# Not_Used.net
KiCad netlist of a schematic drawn in Altium Designer
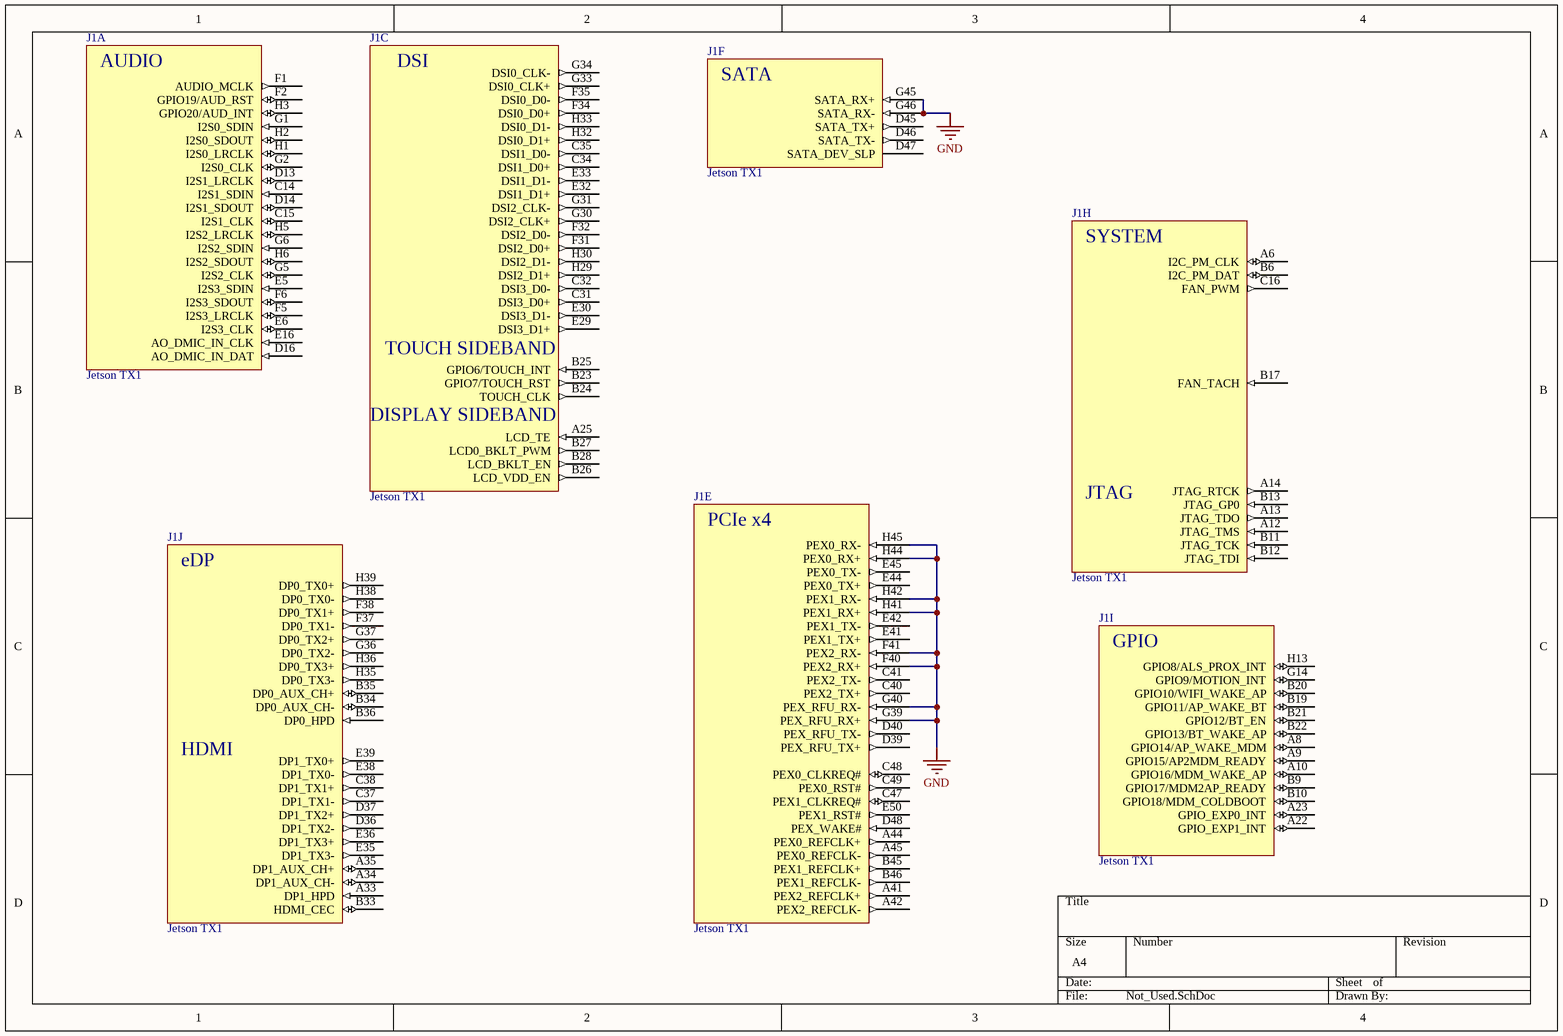
[diagram p0: Not_Used.SchDoc]

(export (version "E")
  (design (tool "Eeschema 10.0.6"))
  (components
    (comp (ref "J1")
      (value "Jetson TX1")
      (footprint "Nvidia Jetson TX1")
      (description "Nvidia computing module")
      (libsource (lib "Modules") (part "NVIDIA_Jetson_TX1"))
    )
  )
  (nets
    (net (code "1") (name "GND") (class "Default")
      (node (ref "J1") (pin "F40") (pinfunction "PEX2_RX+_F40") (pintype "input"))
      (node (ref "J1") (pin "F41") (pinfunction "PEX2_RX-_F41") (pintype "input"))
      (node (ref "J1") (pin "G39") (pinfunction "PEX_RFU_RX+_G39") (pintype "input"))
      (node (ref "J1") (pin "G40") (pinfunction "PEX_RFU_RX-_G40") (pintype "input"))
      (node (ref "J1") (pin "G45") (pinfunction "SATA_RX+_G45") (pintype "input"))
      (node (ref "J1") (pin "G46") (pinfunction "SATA_RX-_G46") (pintype "input"))
      (node (ref "J1") (pin "H41") (pinfunction "PEX1_RX+_H41") (pintype "input"))
      (node (ref "J1") (pin "H42") (pinfunction "PEX1_RX-_H42") (pintype "input"))
      (node (ref "J1") (pin "H44") (pinfunction "PEX0_RX+_H44") (pintype "input"))
      (node (ref "J1") (pin "H45") (pinfunction "PEX0_RX-_H45") (pintype "input"))
    )
    (net (code "2") (name "unconnected-(J1A-AO_DMIC_IN_CLK-PadE16)") (class "Default")
      (node (ref "J1") (pin "E16") (pinfunction "AO_DMIC_IN_CLK_E16") (pintype "input"))
    )
    (net (code "3") (name "unconnected-(J1A-AO_DMIC_IN_DAT-PadD16)") (class "Default")
      (node (ref "J1") (pin "D16") (pinfunction "AO_DMIC_IN_DAT_D16") (pintype "input"))
    )
    (net (code "4") (name "unconnected-(J1A-AUDIO_MCLK-PadF1)") (class "Default")
      (node (ref "J1") (pin "F1") (pinfunction "AUDIO_MCLK_F1") (pintype "output"))
    )
    (net (code "5") (name "unconnected-(J1A-GPIO19{slash}AUD_RST-PadF2)") (class "Default")
      (node (ref "J1") (pin "F2") (pinfunction "GPIO19/AUD_RST_F2") (pintype "bidirectional"))
    )
    (net (code "6") (name "unconnected-(J1A-GPIO20{slash}AUD_INT-PadH3)") (class "Default")
      (node (ref "J1") (pin "H3") (pinfunction "GPIO20/AUD_INT_H3") (pintype "bidirectional"))
    )
    (net (code "7") (name "unconnected-(J1A-I2S0_CLK-PadG2)") (class "Default")
      (node (ref "J1") (pin "G2") (pinfunction "I2S0_CLK_G2") (pintype "bidirectional"))
    )
    (net (code "8") (name "unconnected-(J1A-I2S0_LRCLK-PadH1)") (class "Default")
      (node (ref "J1") (pin "H1") (pinfunction "I2S0_LRCLK_H1") (pintype "bidirectional"))
    )
    (net (code "9") (name "unconnected-(J1A-I2S0_SDIN-PadG1)") (class "Default")
      (node (ref "J1") (pin "G1") (pinfunction "I2S0_SDIN_G1") (pintype "input"))
    )
    (net (code "10") (name "unconnected-(J1A-I2S0_SDOUT-PadH2)") (class "Default")
      (node (ref "J1") (pin "H2") (pinfunction "I2S0_SDOUT_H2") (pintype "bidirectional"))
    )
    (net (code "11") (name "unconnected-(J1A-I2S1_CLK-PadC15)") (class "Default")
      (node (ref "J1") (pin "C15") (pinfunction "I2S1_CLK_C15") (pintype "bidirectional"))
    )
    (net (code "12") (name "unconnected-(J1A-I2S1_LRCLK-PadD13)") (class "Default")
      (node (ref "J1") (pin "D13") (pinfunction "I2S1_LRCLK_D13") (pintype "bidirectional"))
    )
    (net (code "13") (name "unconnected-(J1A-I2S1_SDIN-PadC14)") (class "Default")
      (node (ref "J1") (pin "C14") (pinfunction "I2S1_SDIN_C14") (pintype "input"))
    )
    (net (code "14") (name "unconnected-(J1A-I2S1_SDOUT-PadD14)") (class "Default")
      (node (ref "J1") (pin "D14") (pinfunction "I2S1_SDOUT_D14") (pintype "bidirectional"))
    )
    (net (code "15") (name "unconnected-(J1A-I2S2_CLK-PadG5)") (class "Default")
      (node (ref "J1") (pin "G5") (pinfunction "I2S2_CLK_G5") (pintype "bidirectional"))
    )
    (net (code "16") (name "unconnected-(J1A-I2S2_LRCLK-PadH5)") (class "Default")
      (node (ref "J1") (pin "H5") (pinfunction "I2S2_LRCLK_H5") (pintype "bidirectional"))
    )
    (net (code "17") (name "unconnected-(J1A-I2S2_SDIN-PadG6)") (class "Default")
      (node (ref "J1") (pin "G6") (pinfunction "I2S2_SDIN_G6") (pintype "input"))
    )
    (net (code "18") (name "unconnected-(J1A-I2S2_SDOUT-PadH6)") (class "Default")
      (node (ref "J1") (pin "H6") (pinfunction "I2S2_SDOUT_H6") (pintype "bidirectional"))
    )
    (net (code "19") (name "unconnected-(J1A-I2S3_CLK-PadE6)") (class "Default")
      (node (ref "J1") (pin "E6") (pinfunction "I2S3_CLK_E6") (pintype "bidirectional"))
    )
    (net (code "20") (name "unconnected-(J1A-I2S3_LRCLK-PadF5)") (class "Default")
      (node (ref "J1") (pin "F5") (pinfunction "I2S3_LRCLK_F5") (pintype "bidirectional"))
    )
    (net (code "21") (name "unconnected-(J1A-I2S3_SDIN-PadE5)") (class "Default")
      (node (ref "J1") (pin "E5") (pinfunction "I2S3_SDIN_E5") (pintype "input"))
    )
    (net (code "22") (name "unconnected-(J1A-I2S3_SDOUT-PadF6)") (class "Default")
      (node (ref "J1") (pin "F6") (pinfunction "I2S3_SDOUT_F6") (pintype "bidirectional"))
    )
    (net (code "23") (name "unconnected-(J1C-DSI0_CLK+-PadG33)") (class "Default")
      (node (ref "J1") (pin "G33") (pinfunction "DSI0_CLK+_G33") (pintype "output"))
    )
    (net (code "24") (name "unconnected-(J1C-DSI0_CLK--PadG34)") (class "Default")
      (node (ref "J1") (pin "G34") (pinfunction "DSI0_CLK-_G34") (pintype "output"))
    )
    (net (code "25") (name "unconnected-(J1C-DSI0_D0+-PadF34)") (class "Default")
      (node (ref "J1") (pin "F34") (pinfunction "DSI0_D0+_F34") (pintype "output"))
    )
    (net (code "26") (name "unconnected-(J1C-DSI0_D0--PadF35)") (class "Default")
      (node (ref "J1") (pin "F35") (pinfunction "DSI0_D0-_F35") (pintype "output"))
    )
    (net (code "27") (name "unconnected-(J1C-DSI0_D1+-PadH32)") (class "Default")
      (node (ref "J1") (pin "H32") (pinfunction "DSI0_D1+_H32") (pintype "output"))
    )
    (net (code "28") (name "unconnected-(J1C-DSI0_D1--PadH33)") (class "Default")
      (node (ref "J1") (pin "H33") (pinfunction "DSI0_D1-_H33") (pintype "output"))
    )
    (net (code "29") (name "unconnected-(J1C-DSI1_D0+-PadC34)") (class "Default")
      (node (ref "J1") (pin "C34") (pinfunction "DSI1_D0+_C34") (pintype "output"))
    )
    (net (code "30") (name "unconnected-(J1C-DSI1_D0--PadC35)") (class "Default")
      (node (ref "J1") (pin "C35") (pinfunction "DSI1_D0-_C35") (pintype "output"))
    )
    (net (code "31") (name "unconnected-(J1C-DSI1_D1+-PadE32)") (class "Default")
      (node (ref "J1") (pin "E32") (pinfunction "DSI1_D1+_E32") (pintype "output"))
    )
    (net (code "32") (name "unconnected-(J1C-DSI1_D1--PadE33)") (class "Default")
      (node (ref "J1") (pin "E33") (pinfunction "DSI1_D1-_E33") (pintype "output"))
    )
    (net (code "33") (name "unconnected-(J1C-DSI2_CLK+-PadG30)") (class "Default")
      (node (ref "J1") (pin "G30") (pinfunction "DSI2_CLK+_G30") (pintype "output"))
    )
    (net (code "34") (name "unconnected-(J1C-DSI2_CLK--PadG31)") (class "Default")
      (node (ref "J1") (pin "G31") (pinfunction "DSI2_CLK-_G31") (pintype "output"))
    )
    (net (code "35") (name "unconnected-(J1C-DSI2_D0+-PadF31)") (class "Default")
      (node (ref "J1") (pin "F31") (pinfunction "DSI2_D0+_F31") (pintype "output"))
    )
    (net (code "36") (name "unconnected-(J1C-DSI2_D0--PadF32)") (class "Default")
      (node (ref "J1") (pin "F32") (pinfunction "DSI2_D0-_F32") (pintype "output"))
    )
    (net (code "37") (name "unconnected-(J1C-DSI2_D1+-PadH29)") (class "Default")
      (node (ref "J1") (pin "H29") (pinfunction "DSI2_D1+_H29") (pintype "output"))
    )
    (net (code "38") (name "unconnected-(J1C-DSI2_D1--PadH30)") (class "Default")
      (node (ref "J1") (pin "H30") (pinfunction "DSI2_D1-_H30") (pintype "output"))
    )
    (net (code "39") (name "unconnected-(J1C-DSI3_D0+-PadC31)") (class "Default")
      (node (ref "J1") (pin "C31") (pinfunction "DSI3_D0+_C31") (pintype "output"))
    )
    (net (code "40") (name "unconnected-(J1C-DSI3_D0--PadC32)") (class "Default")
      (node (ref "J1") (pin "C32") (pinfunction "DSI3_D0-_C32") (pintype "output"))
    )
    (net (code "41") (name "unconnected-(J1C-DSI3_D1+-PadE29)") (class "Default")
      (node (ref "J1") (pin "E29") (pinfunction "DSI3_D1+_E29") (pintype "output"))
    )
    (net (code "42") (name "unconnected-(J1C-DSI3_D1--PadE30)") (class "Default")
      (node (ref "J1") (pin "E30") (pinfunction "DSI3_D1-_E30") (pintype "output"))
    )
    (net (code "43") (name "unconnected-(J1C-GPIO6{slash}TOUCH_INT-PadB25)") (class "Default")
      (node (ref "J1") (pin "B25") (pinfunction "GPIO6/TOUCH_INT_B25") (pintype "input"))
    )
    (net (code "44") (name "unconnected-(J1C-GPIO7{slash}TOUCH_RST-PadB23)") (class "Default")
      (node (ref "J1") (pin "B23") (pinfunction "GPIO7/TOUCH_RST_B23") (pintype "output"))
    )
    (net (code "45") (name "unconnected-(J1C-LCD0_BKLT_PWM-PadB27)") (class "Default")
      (node (ref "J1") (pin "B27") (pinfunction "LCD0_BKLT_PWM_B27") (pintype "output"))
    )
    (net (code "46") (name "unconnected-(J1C-LCD_BKLT_EN-PadB28)") (class "Default")
      (node (ref "J1") (pin "B28") (pinfunction "LCD_BKLT_EN_B28") (pintype "output"))
    )
    (net (code "47") (name "unconnected-(J1C-LCD_TE-PadA25)") (class "Default")
      (node (ref "J1") (pin "A25") (pinfunction "LCD_TE_A25") (pintype "input"))
    )
    (net (code "48") (name "unconnected-(J1C-LCD_VDD_EN-PadB26)") (class "Default")
      (node (ref "J1") (pin "B26") (pinfunction "LCD_VDD_EN_B26") (pintype "output"))
    )
    (net (code "49") (name "unconnected-(J1C-TOUCH_CLK-PadB24)") (class "Default")
      (node (ref "J1") (pin "B24") (pinfunction "TOUCH_CLK_B24") (pintype "output"))
    )
    (net (code "50") (name "unconnected-(J1E-PEX0_CLKREQ#-PadC48)") (class "Default")
      (node (ref "J1") (pin "C48") (pinfunction "PEX0_CLKREQ#_C48") (pintype "bidirectional"))
    )
    (net (code "51") (name "unconnected-(J1E-PEX0_REFCLK+-PadA44)") (class "Default")
      (node (ref "J1") (pin "A44") (pinfunction "PEX0_REFCLK+_A44") (pintype "output"))
    )
    (net (code "52") (name "unconnected-(J1E-PEX0_REFCLK--PadA45)") (class "Default")
      (node (ref "J1") (pin "A45") (pinfunction "PEX0_REFCLK-_A45") (pintype "output"))
    )
    (net (code "53") (name "unconnected-(J1E-PEX0_RST#-PadC49)") (class "Default")
      (node (ref "J1") (pin "C49") (pinfunction "PEX0_RST#_C49") (pintype "output"))
    )
    (net (code "54") (name "unconnected-(J1E-PEX0_TX+-PadE44)") (class "Default")
      (node (ref "J1") (pin "E44") (pinfunction "PEX0_TX+_E44") (pintype "output"))
    )
    (net (code "55") (name "unconnected-(J1E-PEX0_TX--PadE45)") (class "Default")
      (node (ref "J1") (pin "E45") (pinfunction "PEX0_TX-_E45") (pintype "output"))
    )
    (net (code "56") (name "unconnected-(J1E-PEX1_CLKREQ#-PadC47)") (class "Default")
      (node (ref "J1") (pin "C47") (pinfunction "PEX1_CLKREQ#_C47") (pintype "bidirectional"))
    )
    (net (code "57") (name "unconnected-(J1E-PEX1_REFCLK+-PadB45)") (class "Default")
      (node (ref "J1") (pin "B45") (pinfunction "PEX1_REFCLK+_B45") (pintype "output"))
    )
    (net (code "58") (name "unconnected-(J1E-PEX1_REFCLK--PadB46)") (class "Default")
      (node (ref "J1") (pin "B46") (pinfunction "PEX1_REFCLK-_B46") (pintype "output"))
    )
    (net (code "59") (name "unconnected-(J1E-PEX1_RST#-PadE50)") (class "Default")
      (node (ref "J1") (pin "E50") (pinfunction "PEX1_RST#_E50") (pintype "output"))
    )
    (net (code "60") (name "unconnected-(J1E-PEX1_TX+-PadE41)") (class "Default")
      (node (ref "J1") (pin "E41") (pinfunction "PEX1_TX+_E41") (pintype "output"))
    )
    (net (code "61") (name "unconnected-(J1E-PEX1_TX--PadE42)") (class "Default")
      (node (ref "J1") (pin "E42") (pinfunction "PEX1_TX-_E42") (pintype "output"))
    )
    (net (code "62") (name "unconnected-(J1E-PEX2_REFCLK+-PadA41)") (class "Default")
      (node (ref "J1") (pin "A41") (pinfunction "PEX2_REFCLK+_A41") (pintype "output"))
    )
    (net (code "63") (name "unconnected-(J1E-PEX2_REFCLK--PadA42)") (class "Default")
      (node (ref "J1") (pin "A42") (pinfunction "PEX2_REFCLK-_A42") (pintype "output"))
    )
    (net (code "64") (name "unconnected-(J1E-PEX2_TX+-PadC40)") (class "Default")
      (node (ref "J1") (pin "C40") (pinfunction "PEX2_TX+_C40") (pintype "output"))
    )
    (net (code "65") (name "unconnected-(J1E-PEX2_TX--PadC41)") (class "Default")
      (node (ref "J1") (pin "C41") (pinfunction "PEX2_TX-_C41") (pintype "output"))
    )
    (net (code "66") (name "unconnected-(J1E-PEX_RFU_TX+-PadD39)") (class "Default")
      (node (ref "J1") (pin "D39") (pinfunction "PEX_RFU_TX+_D39") (pintype "output"))
    )
    (net (code "67") (name "unconnected-(J1E-PEX_RFU_TX--PadD40)") (class "Default")
      (node (ref "J1") (pin "D40") (pinfunction "PEX_RFU_TX-_D40") (pintype "output"))
    )
    (net (code "68") (name "unconnected-(J1E-PEX_WAKE#-PadD48)") (class "Default")
      (node (ref "J1") (pin "D48") (pinfunction "PEX_WAKE#_D48") (pintype "input"))
    )
    (net (code "69") (name "unconnected-(J1F-SATA_DEV_SLP-PadD47)") (class "Default")
      (node (ref "J1") (pin "D47") (pinfunction "SATA_DEV_SLP_D47") (pintype "passive"))
    )
    (net (code "70") (name "unconnected-(J1F-SATA_TX+-PadD45)") (class "Default")
      (node (ref "J1") (pin "D45") (pinfunction "SATA_TX+_D45") (pintype "output"))
    )
    (net (code "71") (name "unconnected-(J1F-SATA_TX--PadD46)") (class "Default")
      (node (ref "J1") (pin "D46") (pinfunction "SATA_TX-_D46") (pintype "output"))
    )
    (net (code "72") (name "unconnected-(J1H-FAN_PWM-PadC16)") (class "Default")
      (node (ref "J1") (pin "C16") (pinfunction "FAN_PWM_C16") (pintype "output"))
    )
    (net (code "73") (name "unconnected-(J1H-FAN_TACH-PadB17)") (class "Default")
      (node (ref "J1") (pin "B17") (pinfunction "FAN_TACH_B17") (pintype "input"))
    )
    (net (code "74") (name "unconnected-(J1H-I2C_PM_CLK-PadA6)") (class "Default")
      (node (ref "J1") (pin "A6") (pinfunction "I2C_PM_CLK_A6") (pintype "bidirectional"))
    )
    (net (code "75") (name "unconnected-(J1H-I2C_PM_DAT-PadB6)") (class "Default")
      (node (ref "J1") (pin "B6") (pinfunction "I2C_PM_DAT_B6") (pintype "bidirectional"))
    )
    (net (code "76") (name "unconnected-(J1H-JTAG_GP0-PadB13)") (class "Default")
      (node (ref "J1") (pin "B13") (pinfunction "JTAG_GP0_B13") (pintype "input"))
    )
    (net (code "77") (name "unconnected-(J1H-JTAG_RTCK-PadA14)") (class "Default")
      (node (ref "J1") (pin "A14") (pinfunction "JTAG_RTCK_A14") (pintype "output"))
    )
    (net (code "78") (name "unconnected-(J1H-JTAG_TCK-PadB11)") (class "Default")
      (node (ref "J1") (pin "B11") (pinfunction "JTAG_TCK_B11") (pintype "input"))
    )
    (net (code "79") (name "unconnected-(J1H-JTAG_TDI-PadB12)") (class "Default")
      (node (ref "J1") (pin "B12") (pinfunction "JTAG_TDI_B12") (pintype "input"))
    )
    (net (code "80") (name "unconnected-(J1H-JTAG_TDO-PadA13)") (class "Default")
      (node (ref "J1") (pin "A13") (pinfunction "JTAG_TDO_A13") (pintype "output"))
    )
    (net (code "81") (name "unconnected-(J1H-JTAG_TMS-PadA12)") (class "Default")
      (node (ref "J1") (pin "A12") (pinfunction "JTAG_TMS_A12") (pintype "input"))
    )
    (net (code "82") (name "unconnected-(J1I-GPIO8{slash}ALS_PROX_INT-PadH13)") (class "Default")
      (node (ref "J1") (pin "H13") (pinfunction "GPIO8/ALS_PROX_INT_H13") (pintype "bidirectional"))
    )
    (net (code "83") (name "unconnected-(J1I-GPIO9{slash}MOTION_INT-PadG14)") (class "Default")
      (node (ref "J1") (pin "G14") (pinfunction "GPIO9/MOTION_INT_G14") (pintype "bidirectional"))
    )
    (net (code "84") (name "unconnected-(J1I-GPIO10{slash}WIFI_WAKE_AP-PadB20)") (class "Default")
      (node (ref "J1") (pin "B20") (pinfunction "GPIO10/WIFI_WAKE_AP_B20") (pintype "bidirectional"))
    )
    (net (code "85") (name "unconnected-(J1I-GPIO11{slash}AP_WAKE_BT-PadB19)") (class "Default")
      (node (ref "J1") (pin "B19") (pinfunction "GPIO11/AP_WAKE_BT_B19") (pintype "bidirectional"))
    )
    (net (code "86") (name "unconnected-(J1I-GPIO12{slash}BT_EN-PadB21)") (class "Default")
      (node (ref "J1") (pin "B21") (pinfunction "GPIO12/BT_EN_B21") (pintype "bidirectional"))
    )
    (net (code "87") (name "unconnected-(J1I-GPIO13{slash}BT_WAKE_AP-PadB22)") (class "Default")
      (node (ref "J1") (pin "B22") (pinfunction "GPIO13/BT_WAKE_AP_B22") (pintype "bidirectional"))
    )
    (net (code "88") (name "unconnected-(J1I-GPIO14{slash}AP_WAKE_MDM-PadA8)") (class "Default")
      (node (ref "J1") (pin "A8") (pinfunction "GPIO14/AP_WAKE_MDM_A8") (pintype "bidirectional"))
    )
    (net (code "89") (name "unconnected-(J1I-GPIO15{slash}AP2MDM_READY-PadA9)") (class "Default")
      (node (ref "J1") (pin "A9") (pinfunction "GPIO15/AP2MDM_READY_A9") (pintype "bidirectional"))
    )
    (net (code "90") (name "unconnected-(J1I-GPIO16{slash}MDM_WAKE_AP-PadA10)") (class "Default")
      (node (ref "J1") (pin "A10") (pinfunction "GPIO16/MDM_WAKE_AP_A10") (pintype "bidirectional"))
    )
    (net (code "91") (name "unconnected-(J1I-GPIO17{slash}MDM2AP_READY-PadB9)") (class "Default")
      (node (ref "J1") (pin "B9") (pinfunction "GPIO17/MDM2AP_READY_B9") (pintype "bidirectional"))
    )
    (net (code "92") (name "unconnected-(J1I-GPIO18{slash}MDM_COLDBOOT-PadB10)") (class "Default")
      (node (ref "J1") (pin "B10") (pinfunction "GPIO18/MDM_COLDBOOT_B10") (pintype "bidirectional"))
    )
    (net (code "93") (name "unconnected-(J1I-GPIO_EXP0_INT-PadA23)") (class "Default")
      (node (ref "J1") (pin "A23") (pinfunction "GPIO_EXP0_INT_A23") (pintype "bidirectional"))
    )
    (net (code "94") (name "unconnected-(J1I-GPIO_EXP1_INT-PadA22)") (class "Default")
      (node (ref "J1") (pin "A22") (pinfunction "GPIO_EXP1_INT_A22") (pintype "bidirectional"))
    )
    (net (code "95") (name "unconnected-(J1J-DP0_AUX_CH+-PadB35)") (class "Default")
      (node (ref "J1") (pin "B35") (pinfunction "DP0_AUX_CH+_B35") (pintype "bidirectional"))
    )
    (net (code "96") (name "unconnected-(J1J-DP0_AUX_CH--PadB34)") (class "Default")
      (node (ref "J1") (pin "B34") (pinfunction "DP0_AUX_CH-_B34") (pintype "bidirectional"))
    )
    (net (code "97") (name "unconnected-(J1J-DP0_HPD-PadB36)") (class "Default")
      (node (ref "J1") (pin "B36") (pinfunction "DP0_HPD_B36") (pintype "input"))
    )
    (net (code "98") (name "unconnected-(J1J-DP0_TX0+-PadH39)") (class "Default")
      (node (ref "J1") (pin "H39") (pinfunction "DP0_TX0+_H39") (pintype "output"))
    )
    (net (code "99") (name "unconnected-(J1J-DP0_TX0--PadH38)") (class "Default")
      (node (ref "J1") (pin "H38") (pinfunction "DP0_TX0-_H38") (pintype "output"))
    )
    (net (code "100") (name "unconnected-(J1J-DP0_TX1+-PadF38)") (class "Default")
      (node (ref "J1") (pin "F38") (pinfunction "DP0_TX1+_F38") (pintype "output"))
    )
    (net (code "101") (name "unconnected-(J1J-DP0_TX1--PadF37)") (class "Default")
      (node (ref "J1") (pin "F37") (pinfunction "DP0_TX1-_F37") (pintype "output"))
    )
    (net (code "102") (name "unconnected-(J1J-DP0_TX2+-PadG37)") (class "Default")
      (node (ref "J1") (pin "G37") (pinfunction "DP0_TX2+_G37") (pintype "output"))
    )
    (net (code "103") (name "unconnected-(J1J-DP0_TX2--PadG36)") (class "Default")
      (node (ref "J1") (pin "G36") (pinfunction "DP0_TX2-_G36") (pintype "output"))
    )
    (net (code "104") (name "unconnected-(J1J-DP0_TX3+-PadH36)") (class "Default")
      (node (ref "J1") (pin "H36") (pinfunction "DP0_TX3+_H36") (pintype "output"))
    )
    (net (code "105") (name "unconnected-(J1J-DP0_TX3--PadH35)") (class "Default")
      (node (ref "J1") (pin "H35") (pinfunction "DP0_TX3-_H35") (pintype "output"))
    )
    (net (code "106") (name "unconnected-(J1J-DP1_AUX_CH+-PadA35)") (class "Default")
      (node (ref "J1") (pin "A35") (pinfunction "DP1_AUX_CH+_A35") (pintype "bidirectional"))
    )
    (net (code "107") (name "unconnected-(J1J-DP1_AUX_CH--PadA34)") (class "Default")
      (node (ref "J1") (pin "A34") (pinfunction "DP1_AUX_CH-_A34") (pintype "bidirectional"))
    )
    (net (code "108") (name "unconnected-(J1J-DP1_HPD-PadA33)") (class "Default")
      (node (ref "J1") (pin "A33") (pinfunction "DP1_HPD_A33") (pintype "input"))
    )
    (net (code "109") (name "unconnected-(J1J-DP1_TX0+-PadE39)") (class "Default")
      (node (ref "J1") (pin "E39") (pinfunction "DP1_TX0+_E39") (pintype "output"))
    )
    (net (code "110") (name "unconnected-(J1J-DP1_TX0--PadE38)") (class "Default")
      (node (ref "J1") (pin "E38") (pinfunction "DP1_TX0-_E38") (pintype "output"))
    )
    (net (code "111") (name "unconnected-(J1J-DP1_TX1+-PadC38)") (class "Default")
      (node (ref "J1") (pin "C38") (pinfunction "DP1_TX1+_C38") (pintype "output"))
    )
    (net (code "112") (name "unconnected-(J1J-DP1_TX1--PadC37)") (class "Default")
      (node (ref "J1") (pin "C37") (pinfunction "DP1_TX1-_C37") (pintype "output"))
    )
    (net (code "113") (name "unconnected-(J1J-DP1_TX2+-PadD37)") (class "Default")
      (node (ref "J1") (pin "D37") (pinfunction "DP1_TX2+_D37") (pintype "output"))
    )
    (net (code "114") (name "unconnected-(J1J-DP1_TX2--PadD36)") (class "Default")
      (node (ref "J1") (pin "D36") (pinfunction "DP1_TX2-_D36") (pintype "output"))
    )
    (net (code "115") (name "unconnected-(J1J-DP1_TX3+-PadE36)") (class "Default")
      (node (ref "J1") (pin "E36") (pinfunction "DP1_TX3+_E36") (pintype "output"))
    )
    (net (code "116") (name "unconnected-(J1J-DP1_TX3--PadE35)") (class "Default")
      (node (ref "J1") (pin "E35") (pinfunction "DP1_TX3-_E35") (pintype "output"))
    )
    (net (code "117") (name "unconnected-(J1J-HDMI_CEC-PadB33)") (class "Default")
      (node (ref "J1") (pin "B33") (pinfunction "HDMI_CEC_B33") (pintype "bidirectional"))
    )
  )
)
